# Flash.net
KiCad netlist of a schematic drawn in Altium Designer
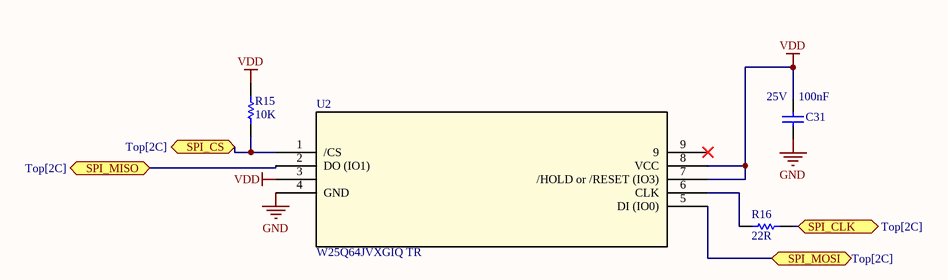
[diagram p0: Flash.SchDoc]

(export (version "E")
  (design (tool "Eeschema 10.0.6"))
  (components
    (comp (ref "C31")
      (value "100nF")
      (footprint "C0402")
      (description "Multilayer Ceramic Capacitors MLCC - SMD/SMT 0402 0.10uF 25volt X5R +/-10%")
      (fields
        (field (name "MANUFACTURER") "Murata")
        (field (name "MANUFACTURER PART NUMBER") "GRM155R61E104KA87D")
        (field (name "VOLTAGE RATING (DC)") "25V")
      )
      (libsource (lib "MCD_PARTS_database") (part "Capacitor"))
    )
    (comp (ref "R15")
      (value "10K")
      (footprint "R0402")
      (description "Resistor, 10K, 0402, +/-0.1%, 1/16W, +/-25ppm/°C")
      (fields (field (name "INTERNAL_PART_NUMBER") "MCD-02551") (field (name "MANUFACTURER") "YAGEO"))
      (libsource (lib "MCD_PARTS_database") (part "Resistor"))
    )
    (comp (ref "R16")
      (value "22R")
      (footprint "R0402")
      (description "Resistor, 22R, 0402, +/-1%, 1/16W")
      (fields (field (name "INTERNAL_PART_NUMBER") "MCD-00189") (field (name "MANUFACTURER") "YAGEO"))
      (libsource (lib "MCD_PARTS_database") (part "Resistor"))
    )
    (comp (ref "U2")
      (value "W25Q64JVXGIQ TR")
      (footprint "DFN_XGIQ TR_WIN-L")
      (description "No Description Available")
      (fields
        (field (name "MANUFACTURER") "Winbond")
        (field (name "COPYRIGHT") "Copyright (C) 2023 Ultra Librarian. All rights reserved.")
      )
      (libsource (lib "missing_parts") (part "W25Q64JVXGIQ TR"))
    )
  )
  (nets
    (net (code "1") (name "/SPI_CLK") (class "Default")
      (node (ref "R16") (pin "1") (pinfunction "1_1") (pintype "passive"))
    )
    (net (code "2") (name "/SPI_CS") (class "Default")
      (node (ref "R15") (pin "1") (pinfunction "1_1") (pintype "passive"))
      (node (ref "U2") (pin "1") (pinfunction "/CS_1") (pintype "passive"))
    )
    (net (code "3") (name "/SPI_MISO") (class "Default")
      (node (ref "U2") (pin "2") (pinfunction "DO_(IO1)_2") (pintype "passive"))
    )
    (net (code "4") (name "/SPI_MOSI") (class "Default")
      (node (ref "U2") (pin "5") (pinfunction "DI_(IO0)_5") (pintype "passive"))
    )
    (net (code "5") (name "GND") (class "Default")
      (node (ref "C31") (pin "1") (pinfunction "1_1") (pintype "passive"))
      (node (ref "U2") (pin "4") (pinfunction "GND_4") (pintype "power_in"))
    )
    (net (code "6") (name "Net-(U2-CLK)") (class "Default")
      (node (ref "R16") (pin "2") (pinfunction "2_2") (pintype "passive"))
      (node (ref "U2") (pin "6") (pinfunction "CLK_6") (pintype "passive"))
    )
    (net (code "7") (name "VDD") (class "Default")
      (node (ref "C31") (pin "2") (pinfunction "2_2") (pintype "passive"))
      (node (ref "R15") (pin "2") (pinfunction "2_2") (pintype "passive"))
      (node (ref "U2") (pin "3") (pinfunction "WP_IO2_3") (pintype "passive"))
      (node (ref "U2") (pin "7") (pinfunction "/HOLD_or_/RESET_(IO3)_7") (pintype "passive"))
      (node (ref "U2") (pin "8") (pinfunction "VCC_8") (pintype "power_in"))
    )
    (net (code "8") (name "unconnected-(U2-Pad9)") (class "Default")
      (node (ref "U2") (pin "9") (pinfunction "9_9") (pintype "passive+no_connect"))
    )
  )
)
